# RowDriver3.net
KiCad netlist of a schematic drawn in EAGLE
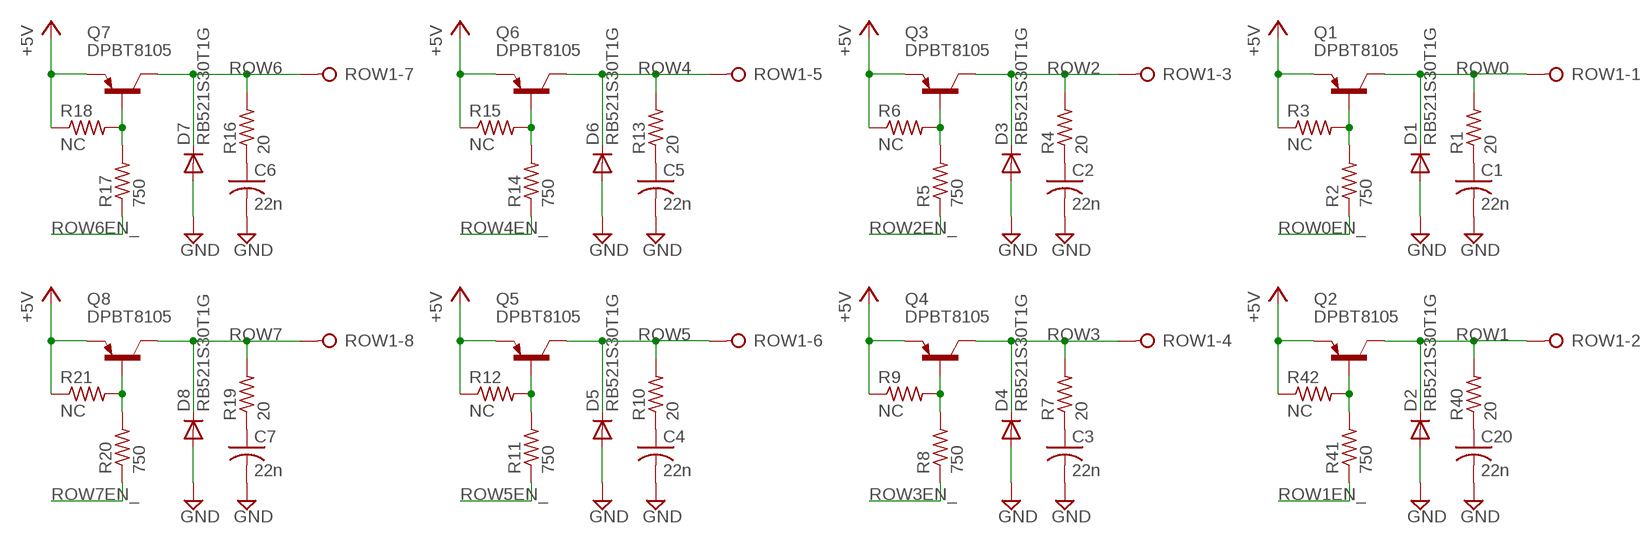
[diagram p0: schematic, sheet 1]

(export (version "E")
  (design (tool "Eeschema 10.0.6"))
  (components
    (comp (ref "C1")
      (value "22n")
      (footprint "eagle-import:C0603")
      (libsource (lib "eagle-import") (part "C-USC0603"))
    )
    (comp (ref "C2")
      (value "22n")
      (footprint "eagle-import:C0603")
      (libsource (lib "eagle-import") (part "C-USC0603"))
    )
    (comp (ref "C3")
      (value "22n")
      (footprint "eagle-import:C0603")
      (libsource (lib "eagle-import") (part "C-USC0603"))
    )
    (comp (ref "C4")
      (value "22n")
      (footprint "eagle-import:C0603")
      (libsource (lib "eagle-import") (part "C-USC0603"))
    )
    (comp (ref "C5")
      (value "22n")
      (footprint "eagle-import:C0603")
      (libsource (lib "eagle-import") (part "C-USC0603"))
    )
    (comp (ref "C6")
      (value "22n")
      (footprint "eagle-import:C0603")
      (libsource (lib "eagle-import") (part "C-USC0603"))
    )
    (comp (ref "C7")
      (value "22n")
      (footprint "eagle-import:C0603")
      (libsource (lib "eagle-import") (part "C-USC0603"))
    )
    (comp (ref "C20")
      (value "22n")
      (footprint "eagle-import:C0603")
      (libsource (lib "eagle-import") (part "C-USC0603"))
    )
    (comp (ref "D1")
      (value "RB521S30T1G")
      (footprint "eagle-import:SOD523")
      (libsource (lib "eagle-import") (part "DIODE-SOD523"))
    )
    (comp (ref "D2")
      (value "RB521S30T1G")
      (footprint "eagle-import:SOD523")
      (libsource (lib "eagle-import") (part "DIODE-SOD523"))
    )
    (comp (ref "D3")
      (value "RB521S30T1G")
      (footprint "eagle-import:SOD523")
      (libsource (lib "eagle-import") (part "DIODE-SOD523"))
    )
    (comp (ref "D4")
      (value "RB521S30T1G")
      (footprint "eagle-import:SOD523")
      (libsource (lib "eagle-import") (part "DIODE-SOD523"))
    )
    (comp (ref "D5")
      (value "RB521S30T1G")
      (footprint "eagle-import:SOD523")
      (libsource (lib "eagle-import") (part "DIODE-SOD523"))
    )
    (comp (ref "D6")
      (value "RB521S30T1G")
      (footprint "eagle-import:SOD523")
      (libsource (lib "eagle-import") (part "DIODE-SOD523"))
    )
    (comp (ref "D7")
      (value "RB521S30T1G")
      (footprint "eagle-import:SOD523")
      (libsource (lib "eagle-import") (part "DIODE-SOD523"))
    )
    (comp (ref "D8")
      (value "RB521S30T1G")
      (footprint "eagle-import:SOD523")
      (libsource (lib "eagle-import") (part "DIODE-SOD523"))
    )
    (comp (ref "Q1")
      (value "DPBT8105")
      (footprint "eagle-import:SOT23")
      (libsource (lib "eagle-import") (part "DPBT8105"))
    )
    (comp (ref "Q2")
      (value "DPBT8105")
      (footprint "eagle-import:SOT23")
      (libsource (lib "eagle-import") (part "DPBT8105"))
    )
    (comp (ref "Q3")
      (value "DPBT8105")
      (footprint "eagle-import:SOT23")
      (libsource (lib "eagle-import") (part "DPBT8105"))
    )
    (comp (ref "Q4")
      (value "DPBT8105")
      (footprint "eagle-import:SOT23")
      (libsource (lib "eagle-import") (part "DPBT8105"))
    )
    (comp (ref "Q5")
      (value "DPBT8105")
      (footprint "eagle-import:SOT23")
      (libsource (lib "eagle-import") (part "DPBT8105"))
    )
    (comp (ref "Q6")
      (value "DPBT8105")
      (footprint "eagle-import:SOT23")
      (libsource (lib "eagle-import") (part "DPBT8105"))
    )
    (comp (ref "Q7")
      (value "DPBT8105")
      (footprint "eagle-import:SOT23")
      (libsource (lib "eagle-import") (part "DPBT8105"))
    )
    (comp (ref "Q8")
      (value "DPBT8105")
      (footprint "eagle-import:SOT23")
      (libsource (lib "eagle-import") (part "DPBT8105"))
    )
    (comp (ref "R1")
      (value "20")
      (footprint "eagle-import:R0603")
      (libsource (lib "eagle-import") (part "R-US_R0603"))
    )
    (comp (ref "R2")
      (value "750")
      (footprint "eagle-import:R0603")
      (libsource (lib "eagle-import") (part "R-US_R0603"))
    )
    (comp (ref "R3")
      (value "NC")
      (footprint "eagle-import:R0603")
      (libsource (lib "eagle-import") (part "R-US_R0603"))
    )
    (comp (ref "R4")
      (value "20")
      (footprint "eagle-import:R0603")
      (libsource (lib "eagle-import") (part "R-US_R0603"))
    )
    (comp (ref "R5")
      (value "750")
      (footprint "eagle-import:R0603")
      (libsource (lib "eagle-import") (part "R-US_R0603"))
    )
    (comp (ref "R6")
      (value "NC")
      (footprint "eagle-import:R0603")
      (libsource (lib "eagle-import") (part "R-US_R0603"))
    )
    (comp (ref "R7")
      (value "20")
      (footprint "eagle-import:R0603")
      (libsource (lib "eagle-import") (part "R-US_R0603"))
    )
    (comp (ref "R8")
      (value "750")
      (footprint "eagle-import:R0603")
      (libsource (lib "eagle-import") (part "R-US_R0603"))
    )
    (comp (ref "R9")
      (value "NC")
      (footprint "eagle-import:R0603")
      (libsource (lib "eagle-import") (part "R-US_R0603"))
    )
    (comp (ref "R10")
      (value "20")
      (footprint "eagle-import:R0603")
      (libsource (lib "eagle-import") (part "R-US_R0603"))
    )
    (comp (ref "R11")
      (value "750")
      (footprint "eagle-import:R0603")
      (libsource (lib "eagle-import") (part "R-US_R0603"))
    )
    (comp (ref "R12")
      (value "NC")
      (footprint "eagle-import:R0603")
      (libsource (lib "eagle-import") (part "R-US_R0603"))
    )
    (comp (ref "R13")
      (value "20")
      (footprint "eagle-import:R0603")
      (libsource (lib "eagle-import") (part "R-US_R0603"))
    )
    (comp (ref "R14")
      (value "750")
      (footprint "eagle-import:R0603")
      (libsource (lib "eagle-import") (part "R-US_R0603"))
    )
    (comp (ref "R15")
      (value "NC")
      (footprint "eagle-import:R0603")
      (libsource (lib "eagle-import") (part "R-US_R0603"))
    )
    (comp (ref "R16")
      (value "20")
      (footprint "eagle-import:R0603")
      (libsource (lib "eagle-import") (part "R-US_R0603"))
    )
    (comp (ref "R17")
      (value "750")
      (footprint "eagle-import:R0603")
      (libsource (lib "eagle-import") (part "R-US_R0603"))
    )
    (comp (ref "R18")
      (value "NC")
      (footprint "eagle-import:R0603")
      (libsource (lib "eagle-import") (part "R-US_R0603"))
    )
    (comp (ref "R19")
      (value "20")
      (footprint "eagle-import:R0603")
      (libsource (lib "eagle-import") (part "R-US_R0603"))
    )
    (comp (ref "R20")
      (value "750")
      (footprint "eagle-import:R0603")
      (libsource (lib "eagle-import") (part "R-US_R0603"))
    )
    (comp (ref "R21")
      (value "NC")
      (footprint "eagle-import:R0603")
      (libsource (lib "eagle-import") (part "R-US_R0603"))
    )
    (comp (ref "R40")
      (value "20")
      (footprint "eagle-import:R0603")
      (libsource (lib "eagle-import") (part "R-US_R0603"))
    )
    (comp (ref "R41")
      (value "750")
      (footprint "eagle-import:R0603")
      (libsource (lib "eagle-import") (part "R-US_R0603"))
    )
    (comp (ref "R42")
      (value "NC")
      (footprint "eagle-import:R0603")
      (libsource (lib "eagle-import") (part "R-US_R0603"))
    )
    (comp (ref "ROW1")
      (value "OSTVN08A150")
      (footprint "eagle-import:OSTVN08")
      (libsource (lib "eagle-import") (part "OSTVN08A150"))
    )
  )
  (nets
    (net (code "1") (name "+5V") (class "Default")
      (node (ref "Q1") (pin "2") (pinfunction "E_2") (pintype "passive"))
      (node (ref "Q2") (pin "2") (pinfunction "E_2") (pintype "passive"))
      (node (ref "Q3") (pin "2") (pinfunction "E_2") (pintype "passive"))
      (node (ref "Q4") (pin "2") (pinfunction "E_2") (pintype "passive"))
      (node (ref "Q5") (pin "2") (pinfunction "E_2") (pintype "passive"))
      (node (ref "Q6") (pin "2") (pinfunction "E_2") (pintype "passive"))
      (node (ref "Q7") (pin "2") (pinfunction "E_2") (pintype "passive"))
      (node (ref "Q8") (pin "2") (pinfunction "E_2") (pintype "passive"))
      (node (ref "R12") (pin "1") (pinfunction "1_1") (pintype "passive"))
      (node (ref "R15") (pin "1") (pinfunction "1_1") (pintype "passive"))
      (node (ref "R18") (pin "1") (pinfunction "1_1") (pintype "passive"))
      (node (ref "R21") (pin "1") (pinfunction "1_1") (pintype "passive"))
      (node (ref "R3") (pin "1") (pinfunction "1_1") (pintype "passive"))
      (node (ref "R42") (pin "1") (pinfunction "1_1") (pintype "passive"))
      (node (ref "R6") (pin "1") (pinfunction "1_1") (pintype "passive"))
      (node (ref "R9") (pin "1") (pinfunction "1_1") (pintype "passive"))
    )
    (net (code "2") (name "/ROW0") (class "Default")
      (node (ref "D1") (pin "C") (pinfunction "C_C") (pintype "passive"))
      (node (ref "Q1") (pin "3") (pinfunction "C_3") (pintype "passive"))
      (node (ref "R1") (pin "2") (pinfunction "2_2") (pintype "passive"))
      (node (ref "ROW1") (pin "1") (pinfunction "KL_1") (pintype "passive"))
    )
    (net (code "3") (name "/ROW0EN_") (class "Default")
      (node (ref "R2") (pin "1") (pinfunction "1_1") (pintype "passive"))
    )
    (net (code "4") (name "/ROW1") (class "Default")
      (node (ref "D2") (pin "C") (pinfunction "C_C") (pintype "passive"))
      (node (ref "Q2") (pin "3") (pinfunction "C_3") (pintype "passive"))
      (node (ref "R40") (pin "2") (pinfunction "2_2") (pintype "passive"))
      (node (ref "ROW1") (pin "2") (pinfunction "KL_2") (pintype "passive"))
    )
    (net (code "5") (name "/ROW1EN_") (class "Default")
      (node (ref "R41") (pin "1") (pinfunction "1_1") (pintype "passive"))
    )
    (net (code "6") (name "/ROW2") (class "Default")
      (node (ref "D3") (pin "C") (pinfunction "C_C") (pintype "passive"))
      (node (ref "Q3") (pin "3") (pinfunction "C_3") (pintype "passive"))
      (node (ref "R4") (pin "2") (pinfunction "2_2") (pintype "passive"))
      (node (ref "ROW1") (pin "3") (pinfunction "KL_3") (pintype "passive"))
    )
    (net (code "7") (name "/ROW2EN_") (class "Default")
      (node (ref "R5") (pin "1") (pinfunction "1_1") (pintype "passive"))
    )
    (net (code "8") (name "/ROW3") (class "Default")
      (node (ref "D4") (pin "C") (pinfunction "C_C") (pintype "passive"))
      (node (ref "Q4") (pin "3") (pinfunction "C_3") (pintype "passive"))
      (node (ref "R7") (pin "2") (pinfunction "2_2") (pintype "passive"))
      (node (ref "ROW1") (pin "4") (pinfunction "KL_4") (pintype "passive"))
    )
    (net (code "9") (name "/ROW3EN_") (class "Default")
      (node (ref "R8") (pin "1") (pinfunction "1_1") (pintype "passive"))
    )
    (net (code "10") (name "/ROW4") (class "Default")
      (node (ref "D6") (pin "C") (pinfunction "C_C") (pintype "passive"))
      (node (ref "Q6") (pin "3") (pinfunction "C_3") (pintype "passive"))
      (node (ref "R13") (pin "2") (pinfunction "2_2") (pintype "passive"))
      (node (ref "ROW1") (pin "5") (pinfunction "KL_5") (pintype "passive"))
    )
    (net (code "11") (name "/ROW4EN_") (class "Default")
      (node (ref "R14") (pin "1") (pinfunction "1_1") (pintype "passive"))
    )
    (net (code "12") (name "/ROW5") (class "Default")
      (node (ref "D5") (pin "C") (pinfunction "C_C") (pintype "passive"))
      (node (ref "Q5") (pin "3") (pinfunction "C_3") (pintype "passive"))
      (node (ref "R10") (pin "2") (pinfunction "2_2") (pintype "passive"))
      (node (ref "ROW1") (pin "6") (pinfunction "KL_6") (pintype "passive"))
    )
    (net (code "13") (name "/ROW5EN_") (class "Default")
      (node (ref "R11") (pin "1") (pinfunction "1_1") (pintype "passive"))
    )
    (net (code "14") (name "/ROW6") (class "Default")
      (node (ref "D7") (pin "C") (pinfunction "C_C") (pintype "passive"))
      (node (ref "Q7") (pin "3") (pinfunction "C_3") (pintype "passive"))
      (node (ref "R16") (pin "2") (pinfunction "2_2") (pintype "passive"))
      (node (ref "ROW1") (pin "7") (pinfunction "KL_7") (pintype "passive"))
    )
    (net (code "15") (name "/ROW6EN_") (class "Default")
      (node (ref "R17") (pin "1") (pinfunction "1_1") (pintype "passive"))
    )
    (net (code "16") (name "/ROW7") (class "Default")
      (node (ref "D8") (pin "C") (pinfunction "C_C") (pintype "passive"))
      (node (ref "Q8") (pin "3") (pinfunction "C_3") (pintype "passive"))
      (node (ref "R19") (pin "2") (pinfunction "2_2") (pintype "passive"))
      (node (ref "ROW1") (pin "8") (pinfunction "KL_8") (pintype "passive"))
    )
    (net (code "17") (name "/ROW7EN_") (class "Default")
      (node (ref "R20") (pin "1") (pinfunction "1_1") (pintype "passive"))
    )
    (net (code "18") (name "GND") (class "Default")
      (node (ref "C1") (pin "2") (pinfunction "2_2") (pintype "passive"))
      (node (ref "C2") (pin "2") (pinfunction "2_2") (pintype "passive"))
      (node (ref "C20") (pin "2") (pinfunction "2_2") (pintype "passive"))
      (node (ref "C3") (pin "2") (pinfunction "2_2") (pintype "passive"))
      (node (ref "C4") (pin "2") (pinfunction "2_2") (pintype "passive"))
      (node (ref "C5") (pin "2") (pinfunction "2_2") (pintype "passive"))
      (node (ref "C6") (pin "2") (pinfunction "2_2") (pintype "passive"))
      (node (ref "C7") (pin "2") (pinfunction "2_2") (pintype "passive"))
      (node (ref "D1") (pin "A") (pinfunction "A_A") (pintype "passive"))
      (node (ref "D2") (pin "A") (pinfunction "A_A") (pintype "passive"))
      (node (ref "D3") (pin "A") (pinfunction "A_A") (pintype "passive"))
      (node (ref "D4") (pin "A") (pinfunction "A_A") (pintype "passive"))
      (node (ref "D5") (pin "A") (pinfunction "A_A") (pintype "passive"))
      (node (ref "D6") (pin "A") (pinfunction "A_A") (pintype "passive"))
      (node (ref "D7") (pin "A") (pinfunction "A_A") (pintype "passive"))
      (node (ref "D8") (pin "A") (pinfunction "A_A") (pintype "passive"))
    )
    (net (code "19") (name "Net-(C1-Pad1)") (class "Default")
      (node (ref "C1") (pin "1") (pinfunction "1_1") (pintype "passive"))
      (node (ref "R1") (pin "1") (pinfunction "1_1") (pintype "passive"))
    )
    (net (code "20") (name "Net-(C2-Pad1)") (class "Default")
      (node (ref "C2") (pin "1") (pinfunction "1_1") (pintype "passive"))
      (node (ref "R4") (pin "1") (pinfunction "1_1") (pintype "passive"))
    )
    (net (code "21") (name "Net-(C3-Pad1)") (class "Default")
      (node (ref "C3") (pin "1") (pinfunction "1_1") (pintype "passive"))
      (node (ref "R7") (pin "1") (pinfunction "1_1") (pintype "passive"))
    )
    (net (code "22") (name "Net-(C4-Pad1)") (class "Default")
      (node (ref "C4") (pin "1") (pinfunction "1_1") (pintype "passive"))
      (node (ref "R10") (pin "1") (pinfunction "1_1") (pintype "passive"))
    )
    (net (code "23") (name "Net-(C5-Pad1)") (class "Default")
      (node (ref "C5") (pin "1") (pinfunction "1_1") (pintype "passive"))
      (node (ref "R13") (pin "1") (pinfunction "1_1") (pintype "passive"))
    )
    (net (code "24") (name "Net-(C6-Pad1)") (class "Default")
      (node (ref "C6") (pin "1") (pinfunction "1_1") (pintype "passive"))
      (node (ref "R16") (pin "1") (pinfunction "1_1") (pintype "passive"))
    )
    (net (code "25") (name "Net-(C7-Pad1)") (class "Default")
      (node (ref "C7") (pin "1") (pinfunction "1_1") (pintype "passive"))
      (node (ref "R19") (pin "1") (pinfunction "1_1") (pintype "passive"))
    )
    (net (code "26") (name "Net-(C20-Pad1)") (class "Default")
      (node (ref "C20") (pin "1") (pinfunction "1_1") (pintype "passive"))
      (node (ref "R40") (pin "1") (pinfunction "1_1") (pintype "passive"))
    )
    (net (code "27") (name "Net-(Q1-B)") (class "Default")
      (node (ref "Q1") (pin "1") (pinfunction "B_1") (pintype "passive"))
      (node (ref "R2") (pin "2") (pinfunction "2_2") (pintype "passive"))
      (node (ref "R3") (pin "2") (pinfunction "2_2") (pintype "passive"))
    )
    (net (code "28") (name "Net-(Q2-B)") (class "Default")
      (node (ref "Q2") (pin "1") (pinfunction "B_1") (pintype "passive"))
      (node (ref "R41") (pin "2") (pinfunction "2_2") (pintype "passive"))
      (node (ref "R42") (pin "2") (pinfunction "2_2") (pintype "passive"))
    )
    (net (code "29") (name "Net-(Q3-B)") (class "Default")
      (node (ref "Q3") (pin "1") (pinfunction "B_1") (pintype "passive"))
      (node (ref "R5") (pin "2") (pinfunction "2_2") (pintype "passive"))
      (node (ref "R6") (pin "2") (pinfunction "2_2") (pintype "passive"))
    )
    (net (code "30") (name "Net-(Q4-B)") (class "Default")
      (node (ref "Q4") (pin "1") (pinfunction "B_1") (pintype "passive"))
      (node (ref "R8") (pin "2") (pinfunction "2_2") (pintype "passive"))
      (node (ref "R9") (pin "2") (pinfunction "2_2") (pintype "passive"))
    )
    (net (code "31") (name "Net-(Q5-B)") (class "Default")
      (node (ref "Q5") (pin "1") (pinfunction "B_1") (pintype "passive"))
      (node (ref "R11") (pin "2") (pinfunction "2_2") (pintype "passive"))
      (node (ref "R12") (pin "2") (pinfunction "2_2") (pintype "passive"))
    )
    (net (code "32") (name "Net-(Q6-B)") (class "Default")
      (node (ref "Q6") (pin "1") (pinfunction "B_1") (pintype "passive"))
      (node (ref "R14") (pin "2") (pinfunction "2_2") (pintype "passive"))
      (node (ref "R15") (pin "2") (pinfunction "2_2") (pintype "passive"))
    )
    (net (code "33") (name "Net-(Q7-B)") (class "Default")
      (node (ref "Q7") (pin "1") (pinfunction "B_1") (pintype "passive"))
      (node (ref "R17") (pin "2") (pinfunction "2_2") (pintype "passive"))
      (node (ref "R18") (pin "2") (pinfunction "2_2") (pintype "passive"))
    )
    (net (code "34") (name "Net-(Q8-B)") (class "Default")
      (node (ref "Q8") (pin "1") (pinfunction "B_1") (pintype "passive"))
      (node (ref "R20") (pin "2") (pinfunction "2_2") (pintype "passive"))
      (node (ref "R21") (pin "2") (pinfunction "2_2") (pintype "passive"))
    )
  )
)
